# DIP-28_C1_IE.net
KiCad netlist of a schematic drawn in EAGLE
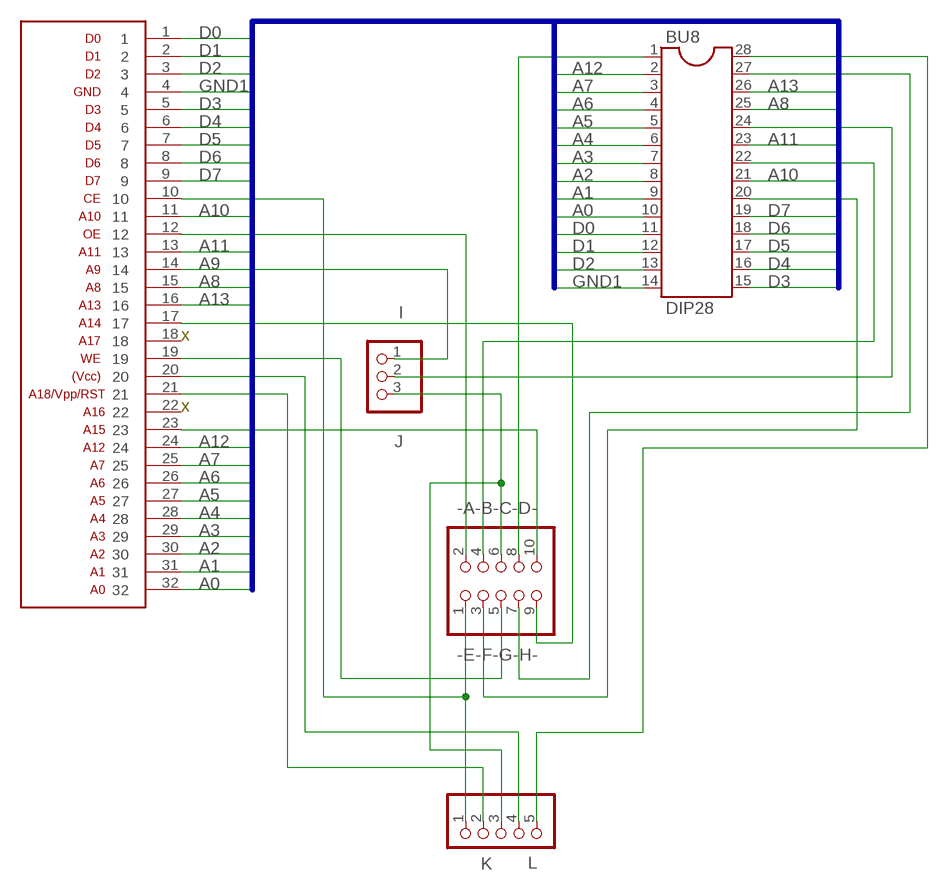
[diagram p0: schematic, sheet 1]

(export (version "E")
  (design (tool "Eeschema 10.0.6"))
  (components
    (comp (ref "-A-B-C-D-")
      (value "-E-F-G-H-")
      (footprint "eagle-import:2X05")
      (libsource (lib "eagle-import") (part "PINHD-2X5"))
    )
    (comp (ref "BU6")
      (value "EZO-BU3")
      (footprint "eagle-import:EZO-BU3")
      (libsource (lib "eagle-import") (part "EZO-BU3"))
    )
    (comp (ref "BU8")
      (value "DIP28")
      (footprint "eagle-import:DIP28P")
      (libsource (lib "eagle-import") (part "DIP28"))
    )
    (comp (ref "I")
      (value "J")
      (footprint "eagle-import:1X03")
      (libsource (lib "eagle-import") (part "PINHD-1X3"))
    )
    (comp (ref "K")
      (value "L")
      (footprint "eagle-import:1X05")
      (libsource (lib "eagle-import") (part "PINHD-1X5"))
    )
  )
  (nets
    (net (code "1") (name "/A0") (class "Default")
      (node (ref "BU6") (pin "32") (pinfunction "32_32") (pintype "bidirectional"))
      (node (ref "BU8") (pin "10") (pinfunction "10_10") (pintype "passive"))
    )
    (net (code "2") (name "/A1") (class "Default")
      (node (ref "BU6") (pin "31") (pinfunction "31_31") (pintype "bidirectional"))
      (node (ref "BU8") (pin "9") (pinfunction "9_9") (pintype "passive"))
    )
    (net (code "3") (name "/A2") (class "Default")
      (node (ref "BU6") (pin "30") (pinfunction "30_30") (pintype "bidirectional"))
      (node (ref "BU8") (pin "8") (pinfunction "8_8") (pintype "passive"))
    )
    (net (code "4") (name "/A3") (class "Default")
      (node (ref "BU6") (pin "29") (pinfunction "29_29") (pintype "bidirectional"))
      (node (ref "BU8") (pin "7") (pinfunction "7_7") (pintype "passive"))
    )
    (net (code "5") (name "/A4") (class "Default")
      (node (ref "BU6") (pin "28") (pinfunction "28_28") (pintype "bidirectional"))
      (node (ref "BU8") (pin "6") (pinfunction "6_6") (pintype "passive"))
    )
    (net (code "6") (name "/A5") (class "Default")
      (node (ref "BU6") (pin "27") (pinfunction "27_27") (pintype "bidirectional"))
      (node (ref "BU8") (pin "5") (pinfunction "5_5") (pintype "passive"))
    )
    (net (code "7") (name "/A6") (class "Default")
      (node (ref "BU6") (pin "26") (pinfunction "26_26") (pintype "bidirectional"))
      (node (ref "BU8") (pin "4") (pinfunction "4_4") (pintype "passive"))
    )
    (net (code "8") (name "/A7") (class "Default")
      (node (ref "BU6") (pin "25") (pinfunction "25_25") (pintype "bidirectional"))
      (node (ref "BU8") (pin "3") (pinfunction "3_3") (pintype "passive"))
    )
    (net (code "9") (name "/A8") (class "Default")
      (node (ref "BU6") (pin "15") (pinfunction "15_15") (pintype "bidirectional"))
      (node (ref "BU8") (pin "25") (pinfunction "25_25") (pintype "passive"))
    )
    (net (code "10") (name "/A9") (class "Default")
      (node (ref "BU6") (pin "14") (pinfunction "14_14") (pintype "bidirectional"))
      (node (ref "I") (pin "1") (pinfunction "1_1") (pintype "passive"))
    )
    (net (code "11") (name "/A10") (class "Default")
      (node (ref "BU6") (pin "11") (pinfunction "11_11") (pintype "bidirectional"))
      (node (ref "BU8") (pin "21") (pinfunction "21_21") (pintype "passive"))
    )
    (net (code "12") (name "/A11") (class "Default")
      (node (ref "BU6") (pin "13") (pinfunction "13_13") (pintype "bidirectional"))
      (node (ref "BU8") (pin "23") (pinfunction "23_23") (pintype "passive"))
    )
    (net (code "13") (name "/A12") (class "Default")
      (node (ref "BU6") (pin "24") (pinfunction "24_24") (pintype "bidirectional"))
      (node (ref "BU8") (pin "2") (pinfunction "2_2") (pintype "passive"))
    )
    (net (code "14") (name "/A13") (class "Default")
      (node (ref "BU6") (pin "16") (pinfunction "16_16") (pintype "bidirectional"))
      (node (ref "BU8") (pin "26") (pinfunction "26_26") (pintype "passive"))
    )
    (net (code "15") (name "/D0") (class "Default")
      (node (ref "BU6") (pin "1") (pinfunction "1_1") (pintype "bidirectional"))
      (node (ref "BU8") (pin "11") (pinfunction "11_11") (pintype "passive"))
    )
    (net (code "16") (name "/D1") (class "Default")
      (node (ref "BU6") (pin "2") (pinfunction "2_2") (pintype "bidirectional"))
      (node (ref "BU8") (pin "12") (pinfunction "12_12") (pintype "passive"))
    )
    (net (code "17") (name "/D2") (class "Default")
      (node (ref "BU6") (pin "3") (pinfunction "3_3") (pintype "bidirectional"))
      (node (ref "BU8") (pin "13") (pinfunction "13_13") (pintype "passive"))
    )
    (net (code "18") (name "/D3") (class "Default")
      (node (ref "BU6") (pin "5") (pinfunction "5_5") (pintype "bidirectional"))
      (node (ref "BU8") (pin "15") (pinfunction "15_15") (pintype "passive"))
    )
    (net (code "19") (name "/D4") (class "Default")
      (node (ref "BU6") (pin "6") (pinfunction "6_6") (pintype "bidirectional"))
      (node (ref "BU8") (pin "16") (pinfunction "16_16") (pintype "passive"))
    )
    (net (code "20") (name "/D5") (class "Default")
      (node (ref "BU6") (pin "7") (pinfunction "7_7") (pintype "bidirectional"))
      (node (ref "BU8") (pin "17") (pinfunction "17_17") (pintype "passive"))
    )
    (net (code "21") (name "/D6") (class "Default")
      (node (ref "BU6") (pin "8") (pinfunction "8_8") (pintype "bidirectional"))
      (node (ref "BU8") (pin "18") (pinfunction "18_18") (pintype "passive"))
    )
    (net (code "22") (name "/D7") (class "Default")
      (node (ref "BU6") (pin "9") (pinfunction "9_9") (pintype "bidirectional"))
      (node (ref "BU8") (pin "19") (pinfunction "19_19") (pintype "passive"))
    )
    (net (code "23") (name "/GND1") (class "Default")
      (node (ref "BU6") (pin "4") (pinfunction "4_4") (pintype "bidirectional"))
      (node (ref "BU8") (pin "14") (pinfunction "14_14") (pintype "passive"))
    )
    (net (code "24") (name "Net-(-A-B-C-D--Pad1)") (class "Default")
      (node (ref "-A-B-C-D-") (pin "1") (pinfunction "1_1") (pintype "passive"))
      (node (ref "BU6") (pin "10") (pinfunction "10_10") (pintype "bidirectional"))
      (node (ref "K") (pin "1") (pinfunction "1_1") (pintype "passive"))
    )
    (net (code "25") (name "Net-(-A-B-C-D--Pad2)") (class "Default")
      (node (ref "-A-B-C-D-") (pin "2") (pinfunction "2_2") (pintype "passive"))
      (node (ref "BU6") (pin "12") (pinfunction "12_12") (pintype "bidirectional"))
    )
    (net (code "26") (name "Net-(-A-B-C-D--Pad3)") (class "Default")
      (node (ref "-A-B-C-D-") (pin "3") (pinfunction "3_3") (pintype "passive"))
      (node (ref "BU8") (pin "20") (pinfunction "20_20") (pintype "passive"))
    )
    (net (code "27") (name "Net-(-A-B-C-D--Pad4)") (class "Default")
      (node (ref "-A-B-C-D-") (pin "4") (pinfunction "4_4") (pintype "passive"))
      (node (ref "BU8") (pin "22") (pinfunction "22_22") (pintype "passive"))
    )
    (net (code "28") (name "Net-(-A-B-C-D--Pad5)") (class "Default")
      (node (ref "-A-B-C-D-") (pin "5") (pinfunction "5_5") (pintype "passive"))
      (node (ref "BU6") (pin "19") (pinfunction "19_19") (pintype "bidirectional"))
    )
    (net (code "29") (name "Net-(-A-B-C-D--Pad6)") (class "Default")
      (node (ref "-A-B-C-D-") (pin "6") (pinfunction "6_6") (pintype "passive"))
      (node (ref "I") (pin "3") (pinfunction "3_3") (pintype "passive"))
      (node (ref "K") (pin "3") (pinfunction "3_3") (pintype "passive"))
    )
    (net (code "30") (name "Net-(-A-B-C-D--Pad7)") (class "Default")
      (node (ref "-A-B-C-D-") (pin "7") (pinfunction "7_7") (pintype "passive"))
      (node (ref "BU8") (pin "27") (pinfunction "27_27") (pintype "passive"))
    )
    (net (code "31") (name "Net-(-A-B-C-D--Pad8)") (class "Default")
      (node (ref "-A-B-C-D-") (pin "8") (pinfunction "8_8") (pintype "passive"))
      (node (ref "BU8") (pin "1") (pinfunction "1_1") (pintype "passive"))
    )
    (net (code "32") (name "Net-(-A-B-C-D--Pad9)") (class "Default")
      (node (ref "-A-B-C-D-") (pin "9") (pinfunction "9_9") (pintype "passive"))
      (node (ref "BU6") (pin "17") (pinfunction "17_17") (pintype "bidirectional"))
    )
    (net (code "33") (name "Net-(-A-B-C-D--Pad10)") (class "Default")
      (node (ref "-A-B-C-D-") (pin "10") (pinfunction "10_10") (pintype "passive"))
      (node (ref "BU6") (pin "23") (pinfunction "23_23") (pintype "bidirectional"))
    )
    (net (code "34") (name "Net-(BU6-Pad20)") (class "Default")
      (node (ref "BU6") (pin "20") (pinfunction "20_20") (pintype "bidirectional"))
      (node (ref "K") (pin "4") (pinfunction "4_4") (pintype "passive"))
    )
    (net (code "35") (name "Net-(BU6-Pad21)") (class "Default")
      (node (ref "BU6") (pin "21") (pinfunction "21_21") (pintype "bidirectional"))
      (node (ref "K") (pin "2") (pinfunction "2_2") (pintype "passive"))
    )
    (net (code "36") (name "Net-(BU8-Pad24)") (class "Default")
      (node (ref "BU8") (pin "24") (pinfunction "24_24") (pintype "passive"))
      (node (ref "I") (pin "2") (pinfunction "2_2") (pintype "passive"))
    )
    (net (code "37") (name "Net-(BU8-Pad28)") (class "Default")
      (node (ref "BU8") (pin "28") (pinfunction "28_28") (pintype "passive"))
      (node (ref "K") (pin "5") (pinfunction "5_5") (pintype "passive"))
    )
    (net (code "38") (name "unconnected-(BU6-Pad18)") (class "Default")
      (node (ref "BU6") (pin "18") (pinfunction "18_18") (pintype "bidirectional"))
    )
    (net (code "39") (name "unconnected-(BU6-Pad22)") (class "Default")
      (node (ref "BU6") (pin "22") (pinfunction "22_22") (pintype "bidirectional"))
    )
  )
)
